# Pi_Breakout.net
KiCad netlist of a schematic drawn in EAGLE
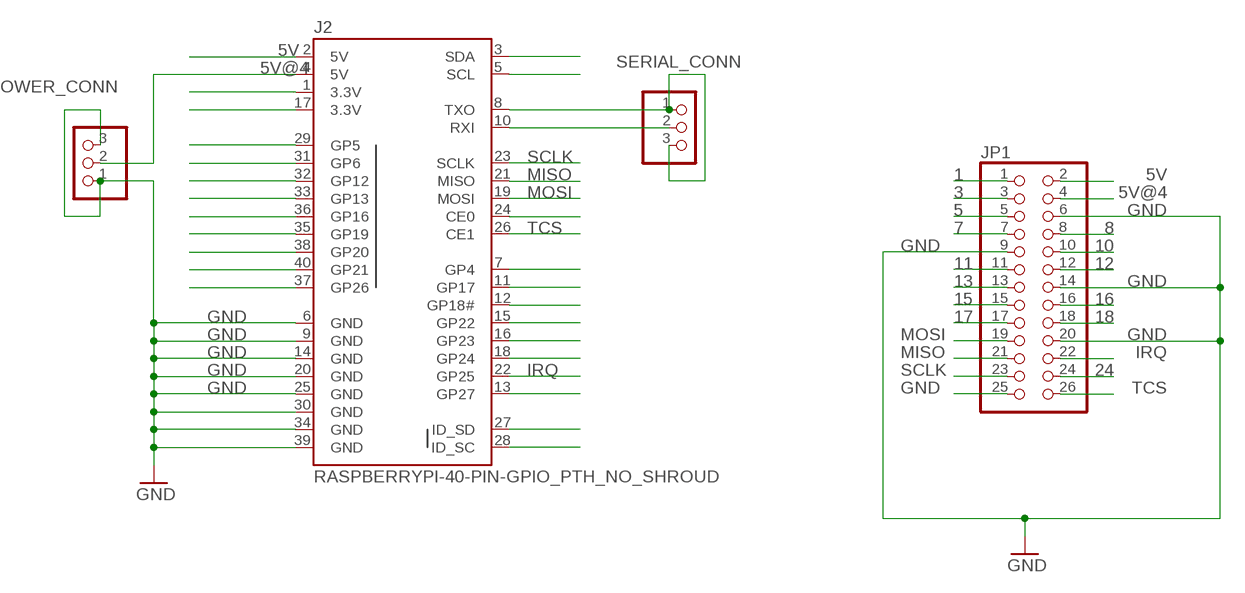
[diagram p0: schematic, sheet 1]

(export (version "E")
  (design (tool "Eeschema 10.0.6"))
  (components
    (comp (ref "J2")
      (value "RASPBERRYPI-40-PIN-GPIO_PTH_NO_SHROUD")
      (footprint "eagle-import:2X20")
      (libsource (lib "eagle-import") (part "RASPBERRYPI-40-PIN-GPIO_PTH_NO_SHROUD"))
    )
    (comp (ref "JP1")
      (value "PINHD-2X13")
      (footprint "eagle-import:2X13")
      (libsource (lib "eagle-import") (part "PINHD-2X13"))
    )
    (comp (ref "POWER_CONN")
      (value "PINHD-1X3")
      (footprint "eagle-import:1X03")
      (libsource (lib "eagle-import") (part "PINHD-1X3"))
    )
    (comp (ref "SERIAL_CONN")
      (value "PINHD-1X3")
      (footprint "eagle-import:1X03")
      (libsource (lib "eagle-import") (part "PINHD-1X3"))
    )
  )
  (nets
    (net (code "1") (name "/1") (class "Default")
      (node (ref "JP1") (pin "1") (pinfunction "1_1") (pintype "passive"))
    )
    (net (code "2") (name "/3") (class "Default")
      (node (ref "JP1") (pin "3") (pinfunction "3_3") (pintype "passive"))
    )
    (net (code "3") (name "/5") (class "Default")
      (node (ref "JP1") (pin "5") (pinfunction "5_5") (pintype "passive"))
    )
    (net (code "4") (name "/5V") (class "Default")
      (node (ref "J2") (pin "2") (pinfunction "5V_2") (pintype "power_in"))
      (node (ref "JP1") (pin "2") (pinfunction "2_2") (pintype "passive"))
    )
    (net (code "5") (name "/5V@4") (class "Default")
      (node (ref "J2") (pin "4") (pinfunction "5V_4") (pintype "power_in"))
      (node (ref "JP1") (pin "4") (pinfunction "4_4") (pintype "passive"))
      (node (ref "POWER_CONN") (pin "2") (pinfunction "2_2") (pintype "passive"))
    )
    (net (code "6") (name "/7") (class "Default")
      (node (ref "JP1") (pin "7") (pinfunction "7_7") (pintype "passive"))
    )
    (net (code "7") (name "/8") (class "Default")
      (node (ref "JP1") (pin "8") (pinfunction "8_8") (pintype "passive"))
    )
    (net (code "8") (name "/10") (class "Default")
      (node (ref "JP1") (pin "10") (pinfunction "10_10") (pintype "passive"))
    )
    (net (code "9") (name "/11") (class "Default")
      (node (ref "JP1") (pin "11") (pinfunction "11_11") (pintype "passive"))
    )
    (net (code "10") (name "/12") (class "Default")
      (node (ref "JP1") (pin "12") (pinfunction "12_12") (pintype "passive"))
    )
    (net (code "11") (name "/13") (class "Default")
      (node (ref "JP1") (pin "13") (pinfunction "13_13") (pintype "passive"))
    )
    (net (code "12") (name "/15") (class "Default")
      (node (ref "JP1") (pin "15") (pinfunction "15_15") (pintype "passive"))
    )
    (net (code "13") (name "/16") (class "Default")
      (node (ref "JP1") (pin "16") (pinfunction "16_16") (pintype "passive"))
    )
    (net (code "14") (name "/17") (class "Default")
      (node (ref "JP1") (pin "17") (pinfunction "17_17") (pintype "passive"))
    )
    (net (code "15") (name "/18") (class "Default")
      (node (ref "JP1") (pin "18") (pinfunction "18_18") (pintype "passive"))
    )
    (net (code "16") (name "/24") (class "Default")
      (node (ref "JP1") (pin "24") (pinfunction "24_24") (pintype "passive"))
    )
    (net (code "17") (name "/IRQ") (class "Default")
      (node (ref "J2") (pin "22") (pinfunction "GP25_22") (pintype "bidirectional"))
      (node (ref "JP1") (pin "22") (pinfunction "22_22") (pintype "passive"))
    )
    (net (code "18") (name "/MISO") (class "Default")
      (node (ref "J2") (pin "21") (pinfunction "MISO_21") (pintype "input"))
      (node (ref "JP1") (pin "21") (pinfunction "21_21") (pintype "passive"))
    )
    (net (code "19") (name "/MOSI") (class "Default")
      (node (ref "J2") (pin "19") (pinfunction "MOSI_19") (pintype "output"))
      (node (ref "JP1") (pin "19") (pinfunction "19_19") (pintype "passive"))
    )
    (net (code "20") (name "/SCLK") (class "Default")
      (node (ref "J2") (pin "23") (pinfunction "SCLK_23") (pintype "output"))
      (node (ref "JP1") (pin "23") (pinfunction "23_23") (pintype "passive"))
    )
    (net (code "21") (name "/TCS") (class "Default")
      (node (ref "J2") (pin "26") (pinfunction "CE1_26") (pintype "output"))
      (node (ref "JP1") (pin "26") (pinfunction "26_26") (pintype "passive"))
    )
    (net (code "22") (name "GND") (class "Default")
      (node (ref "J2") (pin "14") (pinfunction "GND_14") (pintype "power_in"))
      (node (ref "J2") (pin "20") (pinfunction "GND_20") (pintype "power_in"))
      (node (ref "J2") (pin "25") (pinfunction "GND_25") (pintype "power_in"))
      (node (ref "J2") (pin "30") (pinfunction "GND_30") (pintype "power_in"))
      (node (ref "J2") (pin "34") (pinfunction "GND_34") (pintype "power_in"))
      (node (ref "J2") (pin "39") (pinfunction "GND_39") (pintype "power_in"))
      (node (ref "J2") (pin "6") (pinfunction "GND_6") (pintype "power_in"))
      (node (ref "J2") (pin "9") (pinfunction "GND_9") (pintype "power_in"))
      (node (ref "JP1") (pin "14") (pinfunction "14_14") (pintype "passive"))
      (node (ref "JP1") (pin "20") (pinfunction "20_20") (pintype "passive"))
      (node (ref "JP1") (pin "25") (pinfunction "25_25") (pintype "passive"))
      (node (ref "JP1") (pin "6") (pinfunction "6_6") (pintype "passive"))
      (node (ref "JP1") (pin "9") (pinfunction "9_9") (pintype "passive"))
      (node (ref "POWER_CONN") (pin "1") (pinfunction "1_1") (pintype "passive"))
      (node (ref "POWER_CONN") (pin "3") (pinfunction "3_3") (pintype "passive"))
    )
    (net (code "23") (name "Net-(J2-RXI)") (class "Default")
      (node (ref "J2") (pin "10") (pinfunction "RXI_10") (pintype "input"))
      (node (ref "SERIAL_CONN") (pin "2") (pinfunction "2_2") (pintype "passive"))
    )
    (net (code "24") (name "Net-(J2-TXO)") (class "Default")
      (node (ref "J2") (pin "8") (pinfunction "TXO_8") (pintype "output"))
      (node (ref "SERIAL_CONN") (pin "1") (pinfunction "1_1") (pintype "passive"))
      (node (ref "SERIAL_CONN") (pin "3") (pinfunction "3_3") (pintype "passive"))
    )
    (net (code "25") (name "unconnected-(J2-3.3V-Pad1)") (class "Default")
      (node (ref "J2") (pin "1") (pinfunction "3.3V_1") (pintype "power_in"))
    )
    (net (code "26") (name "unconnected-(J2-3.3V-Pad17)") (class "Default")
      (node (ref "J2") (pin "17") (pinfunction "3.3V_17") (pintype "power_in"))
    )
    (net (code "27") (name "unconnected-(J2-CE0-Pad24)") (class "Default")
      (node (ref "J2") (pin "24") (pinfunction "CE0_24") (pintype "output"))
    )
    (net (code "28") (name "unconnected-(J2-GP4-Pad7)") (class "Default")
      (node (ref "J2") (pin "7") (pinfunction "GP4_7") (pintype "bidirectional"))
    )
    (net (code "29") (name "unconnected-(J2-GP5-Pad29)") (class "Default")
      (node (ref "J2") (pin "29") (pinfunction "GP5_29") (pintype "bidirectional"))
    )
    (net (code "30") (name "unconnected-(J2-GP6-Pad31)") (class "Default")
      (node (ref "J2") (pin "31") (pinfunction "GP6_31") (pintype "bidirectional"))
    )
    (net (code "31") (name "unconnected-(J2-GP12-Pad32)") (class "Default")
      (node (ref "J2") (pin "32") (pinfunction "GP12_32") (pintype "bidirectional"))
    )
    (net (code "32") (name "unconnected-(J2-GP13-Pad33)") (class "Default")
      (node (ref "J2") (pin "33") (pinfunction "GP13_33") (pintype "bidirectional"))
    )
    (net (code "33") (name "unconnected-(J2-GP16-Pad36)") (class "Default")
      (node (ref "J2") (pin "36") (pinfunction "GP16_36") (pintype "bidirectional"))
    )
    (net (code "34") (name "unconnected-(J2-GP17-Pad11)") (class "Default")
      (node (ref "J2") (pin "11") (pinfunction "GP17_11") (pintype "bidirectional"))
    )
    (net (code "35") (name "unconnected-(J2-GP18#-Pad12)") (class "Default")
      (node (ref "J2") (pin "12") (pinfunction "GP18#_12") (pintype "bidirectional"))
    )
    (net (code "36") (name "unconnected-(J2-GP19-Pad35)") (class "Default")
      (node (ref "J2") (pin "35") (pinfunction "GP19_35") (pintype "bidirectional"))
    )
    (net (code "37") (name "unconnected-(J2-GP20-Pad38)") (class "Default")
      (node (ref "J2") (pin "38") (pinfunction "GP20_38") (pintype "bidirectional"))
    )
    (net (code "38") (name "unconnected-(J2-GP21-Pad40)") (class "Default")
      (node (ref "J2") (pin "40") (pinfunction "GP21_40") (pintype "bidirectional"))
    )
    (net (code "39") (name "unconnected-(J2-GP22-Pad15)") (class "Default")
      (node (ref "J2") (pin "15") (pinfunction "GP22_15") (pintype "bidirectional"))
    )
    (net (code "40") (name "unconnected-(J2-GP23-Pad16)") (class "Default")
      (node (ref "J2") (pin "16") (pinfunction "GP23_16") (pintype "bidirectional"))
    )
    (net (code "41") (name "unconnected-(J2-GP24-Pad18)") (class "Default")
      (node (ref "J2") (pin "18") (pinfunction "GP24_18") (pintype "bidirectional"))
    )
    (net (code "42") (name "unconnected-(J2-GP26-Pad37)") (class "Default")
      (node (ref "J2") (pin "37") (pinfunction "GP26_37") (pintype "bidirectional"))
    )
    (net (code "43") (name "unconnected-(J2-GP27-Pad13)") (class "Default")
      (node (ref "J2") (pin "13") (pinfunction "GP27_13") (pintype "bidirectional"))
    )
    (net (code "44") (name "unconnected-(J2-ID_SC-Pad28)") (class "Default")
      (node (ref "J2") (pin "28") (pinfunction "ID_SC_28") (pintype "bidirectional"))
    )
    (net (code "45") (name "unconnected-(J2-ID_SD-Pad27)") (class "Default")
      (node (ref "J2") (pin "27") (pinfunction "ID_SD_27") (pintype "bidirectional"))
    )
    (net (code "46") (name "unconnected-(J2-SCL-Pad5)") (class "Default")
      (node (ref "J2") (pin "5") (pinfunction "SCL_5") (pintype "bidirectional"))
    )
    (net (code "47") (name "unconnected-(J2-SDA-Pad3)") (class "Default")
      (node (ref "J2") (pin "3") (pinfunction "SDA_3") (pintype "bidirectional"))
    )
  )
)
